# TC264Sheet.net
KiCad netlist of a schematic drawn in Altium Designer
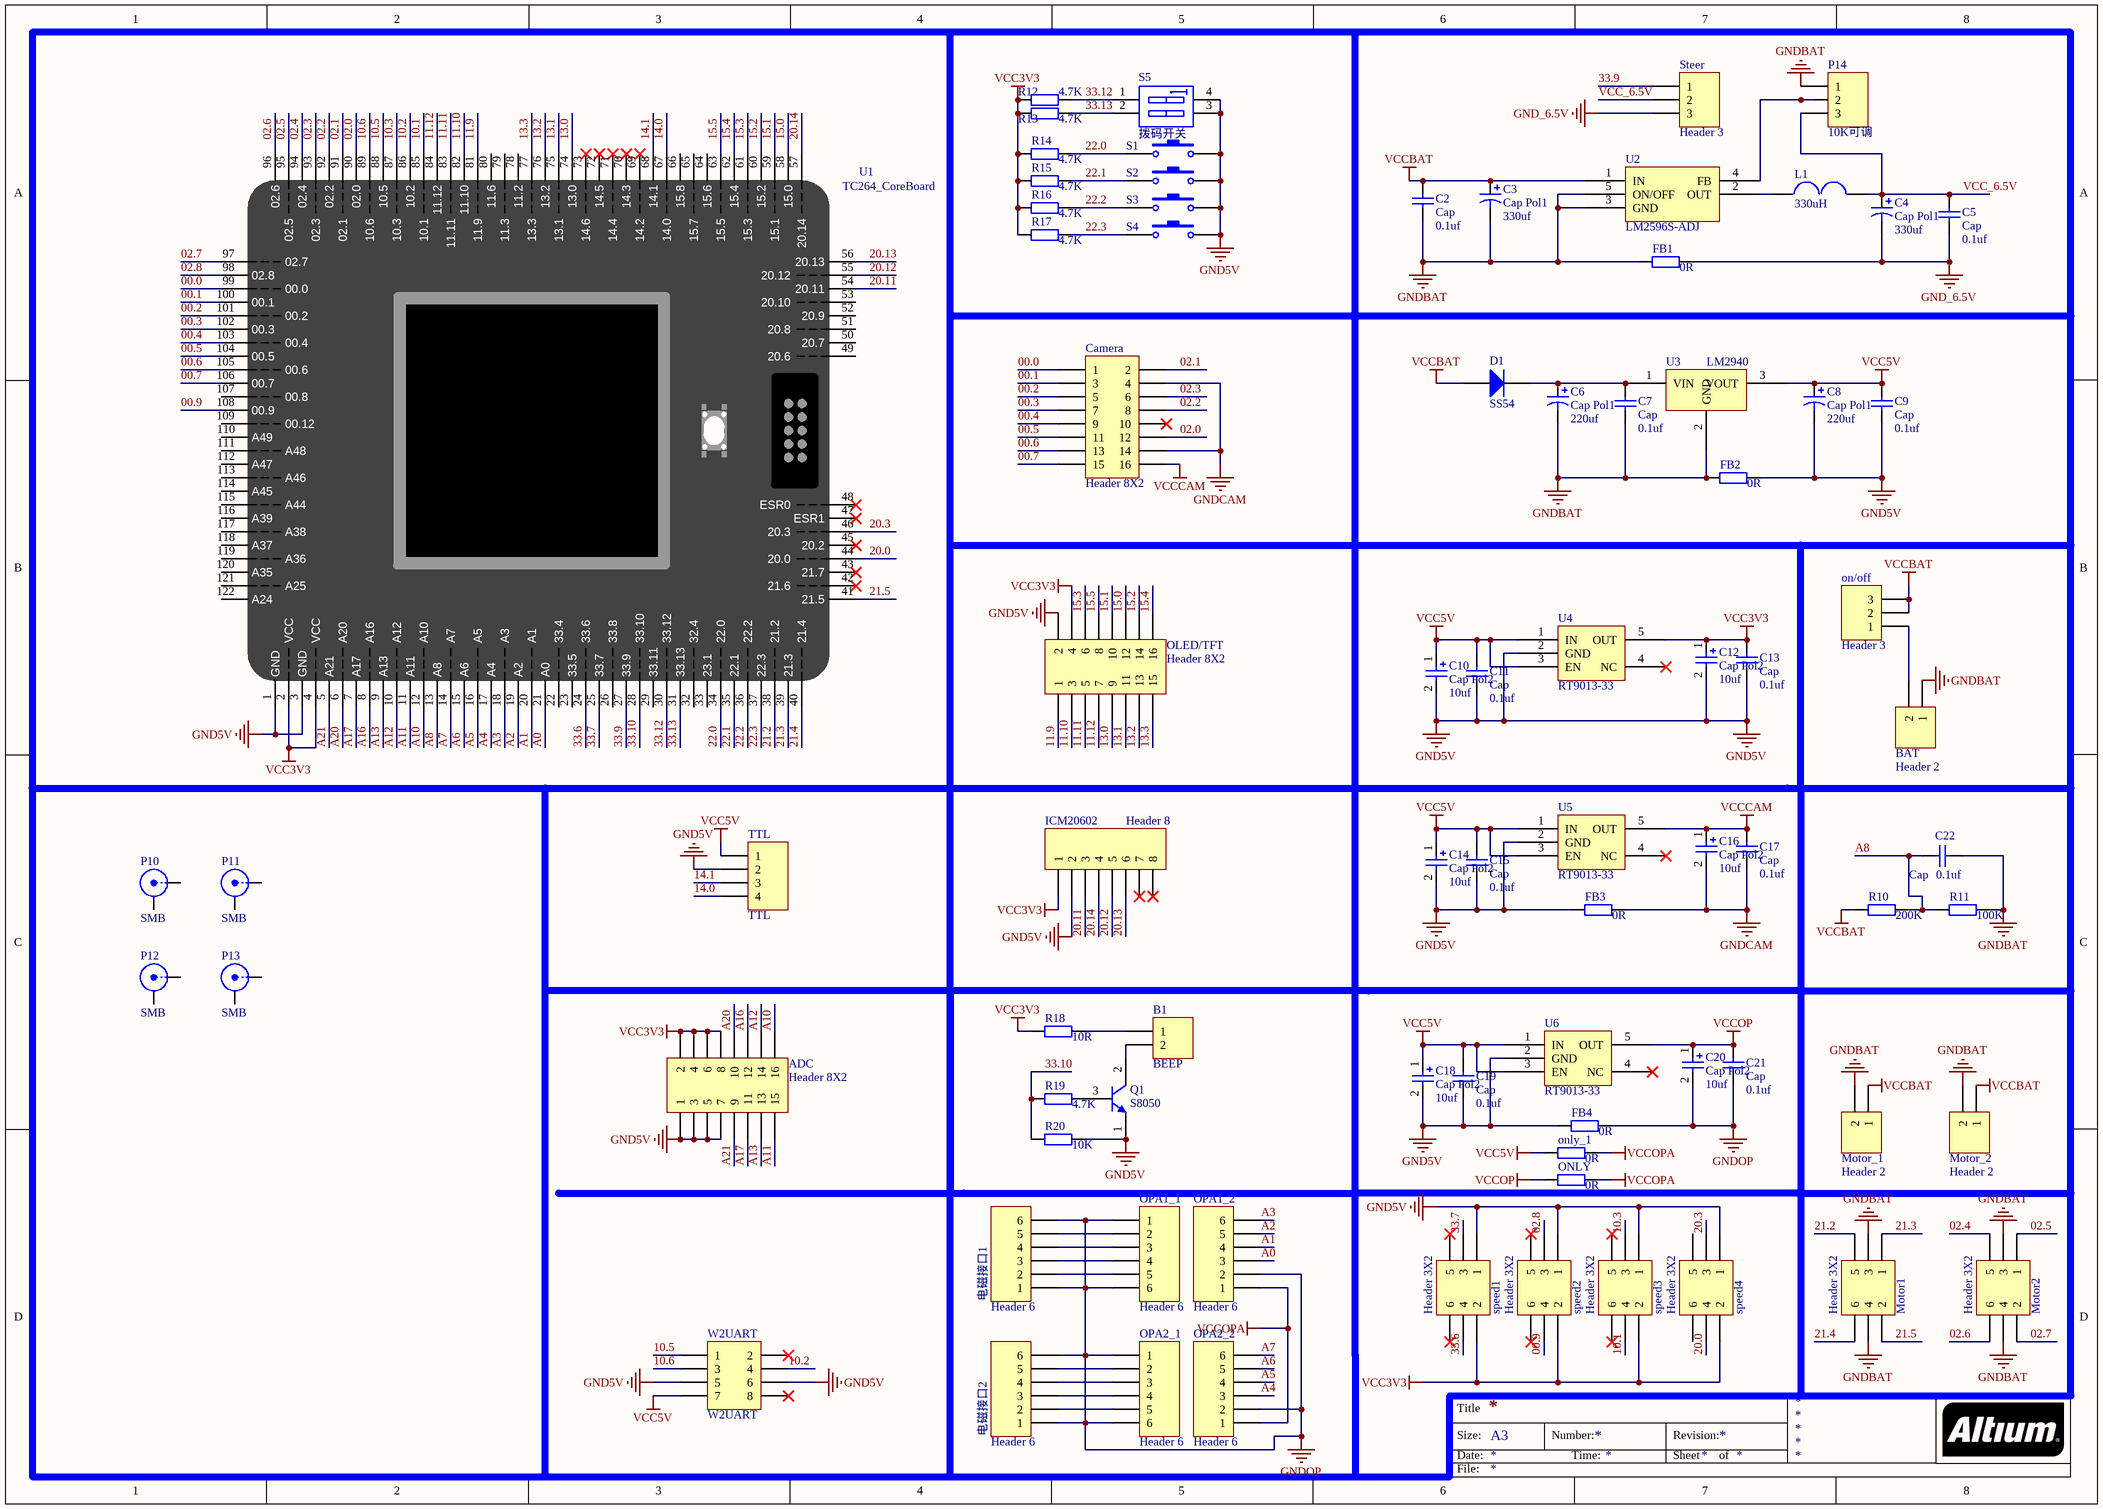
[diagram p0: TC264Sheet.SchDoc]

(export (version "E")
  (design (tool "Eeschema 10.0.6"))
  (components
    (comp (ref "ADC")
      (value "Header 8X2")
      (footprint "HDR2.54-M-LS-2x8P")
      (description "Header, 8-Pin, Dual row")
      (fields (field (name "PUBLISHER") "Altium Limited"))
      (libsource (lib "") (part "Header 8X2_1"))
    )
    (comp (ref "B1")
      (value "BEEP")
      (footprint "9*11mm有源蜂鸣器")
      (description "Header, 2-Pin")
      (fields (field (name "PUBLISHER") "Altium Limited"))
      (libsource (lib "") (part "Header 2_1"))
    )
    (comp (ref "BAT")
      (value "Header 2")
      (footprint "电源端口")
      (description "Header, 2-Pin")
      (fields (field (name "PUBLISHER") "Altium Limited"))
      (libsource (lib "Miscellaneous Connectors") (part "Header 2"))
    )
    (comp (ref "C2")
      (value "Cap")
      (footprint "0603电容_")
      (description "Capacitor")
      (fields (field (name "ALTIUM_VALUE") "0.1uf") (field (name "PUBLISHER") "Altium Limited"))
      (libsource (lib "Miscellaneous Devices") (part "Cap"))
    )
    (comp (ref "C3")
      (value "Cap Pol1")
      (footprint "470UF")
      (description "Polarized Capacitor (Radial)")
      (fields (field (name "ALTIUM_VALUE") "330uf") (field (name "PUBLISHER") "Altium Limited"))
      (libsource (lib "Miscellaneous Devices") (part "Cap Pol1"))
    )
    (comp (ref "C4")
      (value "Cap Pol1")
      (footprint "470UF")
      (description "Polarized Capacitor (Radial)")
      (fields (field (name "ALTIUM_VALUE") "330uf") (field (name "PUBLISHER") "Altium Limited"))
      (libsource (lib "Miscellaneous Devices") (part "Cap Pol1"))
    )
    (comp (ref "C5")
      (value "Cap")
      (footprint "0603电容_")
      (description "Capacitor")
      (fields (field (name "ALTIUM_VALUE") "0.1uf") (field (name "PUBLISHER") "Altium Limited"))
      (libsource (lib "Miscellaneous Devices") (part "Cap"))
    )
    (comp (ref "C6")
      (value "Cap Pol1")
      (footprint "470UF")
      (description "Polarized Capacitor (Radial)")
      (fields (field (name "ALTIUM_VALUE") "220uf") (field (name "PUBLISHER") "Altium Limited"))
      (libsource (lib "Miscellaneous Devices") (part "Cap Pol1"))
    )
    (comp (ref "C7")
      (value "Cap")
      (footprint "0603电容_")
      (description "Capacitor")
      (fields (field (name "ALTIUM_VALUE") "0.1uf") (field (name "PUBLISHER") "Altium Limited"))
      (libsource (lib "Miscellaneous Devices") (part "Cap"))
    )
    (comp (ref "C8")
      (value "Cap Pol1")
      (footprint "470UF")
      (description "Polarized Capacitor (Radial)")
      (fields (field (name "ALTIUM_VALUE") "220uf") (field (name "PUBLISHER") "Altium Limited"))
      (libsource (lib "Miscellaneous Devices") (part "Cap Pol1"))
    )
    (comp (ref "C9")
      (value "Cap")
      (footprint "0603电容_")
      (description "Capacitor")
      (fields (field (name "ALTIUM_VALUE") "0.1uf") (field (name "PUBLISHER") "Altium Limited"))
      (libsource (lib "Miscellaneous Devices") (part "Cap"))
    )
    (comp (ref "C10")
      (value "Cap Pol2")
      (footprint "10UF钽电容")
      (description "Polarized Capacitor (Axial)")
      (fields (field (name "ALTIUM_VALUE") "10uf") (field (name "PUBLISHER") "Altium Limited"))
      (libsource (lib "Miscellaneous Devices") (part "Cap Pol2"))
    )
    (comp (ref "C11")
      (value "Cap")
      (footprint "0603电容_")
      (description "Capacitor")
      (fields (field (name "ALTIUM_VALUE") "0.1uf") (field (name "PUBLISHER") "Altium Limited"))
      (libsource (lib "Miscellaneous Devices") (part "Cap"))
    )
    (comp (ref "C12")
      (value "Cap Pol2")
      (footprint "10UF钽电容")
      (description "Polarized Capacitor (Axial)")
      (fields (field (name "ALTIUM_VALUE") "10uf") (field (name "PUBLISHER") "Altium Limited"))
      (libsource (lib "Miscellaneous Devices") (part "Cap Pol2"))
    )
    (comp (ref "C13")
      (value "Cap")
      (footprint "0603电容_")
      (description "Capacitor")
      (fields (field (name "ALTIUM_VALUE") "0.1uf") (field (name "PUBLISHER") "Altium Limited"))
      (libsource (lib "Miscellaneous Devices") (part "Cap"))
    )
    (comp (ref "C14")
      (value "Cap Pol2")
      (footprint "10UF钽电容")
      (description "Polarized Capacitor (Axial)")
      (fields (field (name "ALTIUM_VALUE") "10uf") (field (name "PUBLISHER") "Altium Limited"))
      (libsource (lib "Miscellaneous Devices") (part "Cap Pol2"))
    )
    (comp (ref "C15")
      (value "Cap")
      (footprint "0603电容_")
      (description "Capacitor")
      (fields (field (name "ALTIUM_VALUE") "0.1uf") (field (name "PUBLISHER") "Altium Limited"))
      (libsource (lib "Miscellaneous Devices") (part "Cap"))
    )
    (comp (ref "C16")
      (value "Cap Pol2")
      (footprint "10UF钽电容")
      (description "Polarized Capacitor (Axial)")
      (fields (field (name "ALTIUM_VALUE") "10uf") (field (name "PUBLISHER") "Altium Limited"))
      (libsource (lib "Miscellaneous Devices") (part "Cap Pol2"))
    )
    (comp (ref "C17")
      (value "Cap")
      (footprint "0603电容_")
      (description "Capacitor")
      (fields (field (name "ALTIUM_VALUE") "0.1uf") (field (name "PUBLISHER") "Altium Limited"))
      (libsource (lib "Miscellaneous Devices") (part "Cap"))
    )
    (comp (ref "C18")
      (value "Cap Pol2")
      (footprint "10UF钽电容")
      (description "Polarized Capacitor (Axial)")
      (fields (field (name "ALTIUM_VALUE") "10uf") (field (name "PUBLISHER") "Altium Limited"))
      (libsource (lib "Miscellaneous Devices") (part "Cap Pol2"))
    )
    (comp (ref "C19")
      (value "Cap")
      (footprint "0603电容_")
      (description "Capacitor")
      (fields (field (name "ALTIUM_VALUE") "0.1uf") (field (name "PUBLISHER") "Altium Limited"))
      (libsource (lib "Miscellaneous Devices") (part "Cap"))
    )
    (comp (ref "C20")
      (value "Cap Pol2")
      (footprint "10UF钽电容")
      (description "Polarized Capacitor (Axial)")
      (fields (field (name "ALTIUM_VALUE") "10uf") (field (name "PUBLISHER") "Altium Limited"))
      (libsource (lib "Miscellaneous Devices") (part "Cap Pol2"))
    )
    (comp (ref "C21")
      (value "Cap")
      (footprint "0603电容_")
      (description "Capacitor")
      (fields (field (name "ALTIUM_VALUE") "0.1uf") (field (name "PUBLISHER") "Altium Limited"))
      (libsource (lib "Miscellaneous Devices") (part "Cap"))
    )
    (comp (ref "C22")
      (value "Cap")
      (footprint "0603电容_")
      (description "Capacitor")
      (fields (field (name "ALTIUM_VALUE") "0.1uf") (field (name "PUBLISHER") "Altium Limited"))
      (libsource (lib "Miscellaneous Devices") (part "Cap"))
    )
    (comp (ref "Camera")
      (value "Header 8X2")
      (footprint "HDR2.54-M-LS-2x8P")
      (description "Header, 8-Pin, Dual row")
      (fields (field (name "PUBLISHER") "Altium Limited"))
      (libsource (lib "Miscellaneous Connectors") (part "Header 8X2"))
    )
    (comp (ref "D1")
      (value "SS54")
      (footprint "in5819_SLFK")
      (description "3 Amp General Purpose Rectifier")
      (fields (field (name "PUBLISHER") "Altium Limited"))
      (libsource (lib "Miscellaneous Devices") (part "Diode 1N5404"))
    )
    (comp (ref "FB1")
      (value "0R")
      (footprint "0603电阻_")
      (description "Resistor")
      (fields (field (name "PUBLISHER") "Altium Limited"))
      (libsource (lib "Miscellaneous Devices") (part "Res2"))
    )
    (comp (ref "FB2")
      (value "0R")
      (footprint "0603电阻_")
      (description "Resistor")
      (fields (field (name "PUBLISHER") "Altium Limited"))
      (libsource (lib "Miscellaneous Devices") (part "Res2"))
    )
    (comp (ref "FB3")
      (value "0R")
      (footprint "0603电阻_")
      (description "Resistor")
      (fields (field (name "PUBLISHER") "Altium Limited"))
      (libsource (lib "Miscellaneous Devices") (part "Res2"))
    )
    (comp (ref "FB4")
      (value "0R")
      (footprint "0603电阻_")
      (description "Resistor")
      (fields (field (name "PUBLISHER") "Altium Limited"))
      (libsource (lib "Miscellaneous Devices") (part "Res2"))
    )
    (comp (ref "ICM20602")
      (value "Header 8")
      (footprint "HDR1X8")
      (description "Header, 8-Pin")
      (fields (field (name "PUBLISHER") "Altium Limited"))
      (libsource (lib "Miscellaneous Connectors") (part "Header 8"))
    )
    (comp (ref "L1") (value "330uH") (footprint "330uH") (libsource (lib "TC264Schlib") (part "330uH")))
    (comp (ref "Motor1")
      (value "Header 3X2")
      (footprint "HDR2.54-M-LS-2x3P")
      (description "Header, 3-Pin, Dual row")
      (fields (field (name "PUBLISHER") "Altium Limited"))
      (libsource (lib "Miscellaneous Connectors") (part "Header 3X2"))
    )
    (comp (ref "Motor2")
      (value "Header 3X2")
      (footprint "HDR2.54-M-LS-2x3P")
      (description "Header, 3-Pin, Dual row")
      (fields (field (name "PUBLISHER") "Altium Limited"))
      (libsource (lib "Miscellaneous Connectors") (part "Header 3X2"))
    )
    (comp (ref "Motor_1")
      (value "Header 2")
      (footprint "电源端口")
      (description "Header, 2-Pin")
      (fields (field (name "PUBLISHER") "Altium Limited"))
      (libsource (lib "Miscellaneous Connectors") (part "Header 2"))
    )
    (comp (ref "Motor_2")
      (value "Header 2")
      (footprint "电源端口")
      (description "Header, 2-Pin")
      (fields (field (name "PUBLISHER") "Altium Limited"))
      (libsource (lib "Miscellaneous Connectors") (part "Header 2"))
    )
    (comp (ref "OLED/TFT")
      (value "Header 8X2")
      (footprint "HDR2.54-M-LS-2x8P")
      (description "Header, 8-Pin, Dual row")
      (fields (field (name "PUBLISHER") "Altium Limited"))
      (libsource (lib "") (part "Header 8X2_1"))
    )
    (comp (ref "on/off")
      (value "Header 3")
      (footprint "小扭子开关")
      (description "Header, 3-Pin")
      (fields (field (name "PUBLISHER") "Altium Limited"))
      (libsource (lib "Miscellaneous Connectors") (part "Header 3"))
    )
    (comp (ref "ONLY")
      (value "0R")
      (footprint "0603电阻_")
      (description "Resistor")
      (fields (field (name "PUBLISHER") "Altium Limited"))
      (libsource (lib "Miscellaneous Devices") (part "Res2"))
    )
    (comp (ref "only_1")
      (value "0R")
      (footprint "0603电阻_")
      (description "Resistor")
      (fields (field (name "PUBLISHER") "Altium Limited"))
      (libsource (lib "Miscellaneous Devices") (part "Res2"))
    )
    (comp (ref "OPA1_1")
      (value "Header 6")
      (footprint "HDR1X6")
      (description "Header, 6-Pin")
      (fields (field (name "PUBLISHER") "Altium Limited"))
      (libsource (lib "") (part "Header 6_1"))
    )
    (comp (ref "OPA1_2")
      (value "Header 6")
      (footprint "HDR1X6")
      (description "Header, 6-Pin")
      (fields (field (name "PUBLISHER") "Altium Limited"))
      (libsource (lib "Miscellaneous Connectors") (part "Header 6"))
    )
    (comp (ref "OPA2_1")
      (value "Header 6")
      (footprint "HDR1X6")
      (description "Header, 6-Pin")
      (fields (field (name "PUBLISHER") "Altium Limited"))
      (libsource (lib "") (part "Header 6_1"))
    )
    (comp (ref "OPA2_2")
      (value "Header 6")
      (footprint "HDR1X6")
      (description "Header, 6-Pin")
      (fields (field (name "PUBLISHER") "Altium Limited"))
      (libsource (lib "Miscellaneous Connectors") (part "Header 6"))
    )
    (comp (ref "P10")
      (value "SMB")
      (footprint "螺丝孔")
      (description "SMB Straight Connector")
      (fields (field (name "PUBLISHER") "Altium Limited"))
      (libsource (lib "Miscellaneous Connectors") (part "SMB"))
    )
    (comp (ref "P11")
      (value "SMB")
      (footprint "螺丝孔")
      (description "SMB Straight Connector")
      (fields (field (name "PUBLISHER") "Altium Limited"))
      (libsource (lib "Miscellaneous Connectors") (part "SMB"))
    )
    (comp (ref "P12")
      (value "SMB")
      (footprint "螺丝孔")
      (description "SMB Straight Connector")
      (fields (field (name "PUBLISHER") "Altium Limited"))
      (libsource (lib "Miscellaneous Connectors") (part "SMB"))
    )
    (comp (ref "P13")
      (value "SMB")
      (footprint "螺丝孔")
      (description "SMB Straight Connector")
      (fields (field (name "PUBLISHER") "Altium Limited"))
      (libsource (lib "Miscellaneous Connectors") (part "SMB"))
    )
    (comp (ref "P14")
      (value "10K可调")
      (footprint "白兰可调电阻")
      (description "Header, 3-Pin")
      (fields (field (name "PUBLISHER") "Altium Limited"))
      (libsource (lib "") (part "Header 3_1"))
    )
    (comp (ref "Q1")
      (value "S8050")
      (footprint "SI2302")
      (description "NPN General Purpose Amplifier")
      (fields (field (name "PUBLISHER") "Altium Limited"))
      (libsource (lib "Miscellaneous Devices") (part "2N3904"))
    )
    (comp (ref "R10")
      (value "200K")
      (footprint "0603电阻_")
      (description "Resistor")
      (fields (field (name "PUBLISHER") "Altium Limited"))
      (libsource (lib "Miscellaneous Devices") (part "Res2"))
    )
    (comp (ref "R11")
      (value "100K")
      (footprint "0603电阻_")
      (description "Resistor")
      (fields (field (name "PUBLISHER") "Altium Limited"))
      (libsource (lib "Miscellaneous Devices") (part "Res2"))
    )
    (comp (ref "R12")
      (value "4.7K")
      (footprint "0603电阻_")
      (description "Resistor")
      (fields (field (name "PUBLISHER") "Altium Limited"))
      (libsource (lib "Miscellaneous Devices") (part "Res2"))
    )
    (comp (ref "R13")
      (value "4.7K")
      (footprint "0603电阻_")
      (description "Resistor")
      (fields (field (name "PUBLISHER") "Altium Limited"))
      (libsource (lib "Miscellaneous Devices") (part "Res2"))
    )
    (comp (ref "R14")
      (value "4.7K")
      (footprint "0603电阻_")
      (description "Resistor")
      (fields (field (name "PUBLISHER") "Altium Limited"))
      (libsource (lib "Miscellaneous Devices") (part "Res2"))
    )
    (comp (ref "R15")
      (value "4.7K")
      (footprint "0603电阻_")
      (description "Resistor")
      (fields (field (name "PUBLISHER") "Altium Limited"))
      (libsource (lib "Miscellaneous Devices") (part "Res2"))
    )
    (comp (ref "R16")
      (value "4.7K")
      (footprint "0603电阻_")
      (description "Resistor")
      (fields (field (name "PUBLISHER") "Altium Limited"))
      (libsource (lib "Miscellaneous Devices") (part "Res2"))
    )
    (comp (ref "R17")
      (value "4.7K")
      (footprint "0603电阻_")
      (description "Resistor")
      (fields (field (name "PUBLISHER") "Altium Limited"))
      (libsource (lib "Miscellaneous Devices") (part "Res2"))
    )
    (comp (ref "R18")
      (value "10R")
      (footprint "0603电阻_")
      (description "Resistor")
      (fields (field (name "PUBLISHER") "Altium Limited"))
      (libsource (lib "Miscellaneous Devices") (part "Res2"))
    )
    (comp (ref "R19")
      (value "4.7K")
      (footprint "0603电阻_")
      (description "Resistor")
      (fields (field (name "PUBLISHER") "Altium Limited"))
      (libsource (lib "Miscellaneous Devices") (part "Res2"))
    )
    (comp (ref "R20")
      (value "10K")
      (footprint "0603电阻_")
      (description "Resistor")
      (fields (field (name "PUBLISHER") "Altium Limited"))
      (libsource (lib "Miscellaneous Devices") (part "Res2"))
    )
    (comp (ref "S1")
      (value "~")
      (footprint "3*4*2贴片轻触按键")
      (description "Switch")
      (fields (field (name "PUBLISHER") "Altium Limited"))
      (libsource (lib "Miscellaneous Devices") (part "SW-PB"))
    )
    (comp (ref "S2")
      (value "~")
      (footprint "3*4*2贴片轻触按键")
      (description "Switch")
      (fields (field (name "PUBLISHER") "Altium Limited"))
      (libsource (lib "Miscellaneous Devices") (part "SW-PB"))
    )
    (comp (ref "S3")
      (value "~")
      (footprint "3*4*2贴片轻触按键")
      (description "Switch")
      (fields (field (name "PUBLISHER") "Altium Limited"))
      (libsource (lib "Miscellaneous Devices") (part "SW-PB"))
    )
    (comp (ref "S4")
      (value "~")
      (footprint "3*4*2贴片轻触按键")
      (description "Switch")
      (fields (field (name "PUBLISHER") "Altium Limited"))
      (libsource (lib "Miscellaneous Devices") (part "SW-PB"))
    )
    (comp (ref "S5")
      (value "拨码开关")
      (footprint "2pin拨码开关2.54_SMT")
      (description "DIP Switch, 2 Position, SPST")
      (fields (field (name "PUBLISHER") "Altium Limited"))
      (libsource (lib "Miscellaneous Devices") (part "SW DIP-2"))
    )
    (comp (ref "speed1")
      (value "Header 3X2")
      (footprint "HDR2.54-M-LS-2x3P")
      (description "Header, 3-Pin, Dual row")
      (fields (field (name "PUBLISHER") "Altium Limited"))
      (libsource (lib "Miscellaneous Connectors") (part "Header 3X2"))
    )
    (comp (ref "speed2")
      (value "Header 3X2")
      (footprint "HDR2.54-M-LS-2x3P")
      (description "Header, 3-Pin, Dual row")
      (fields (field (name "PUBLISHER") "Altium Limited"))
      (libsource (lib "Miscellaneous Connectors") (part "Header 3X2"))
    )
    (comp (ref "speed3")
      (value "Header 3X2")
      (footprint "HDR2.54-M-LS-2x3P")
      (description "Header, 3-Pin, Dual row")
      (fields (field (name "PUBLISHER") "Altium Limited"))
      (libsource (lib "Miscellaneous Connectors") (part "Header 3X2"))
    )
    (comp (ref "speed4")
      (value "Header 3X2")
      (footprint "HDR2.54-M-LS-2x3P")
      (description "Header, 3-Pin, Dual row")
      (fields (field (name "PUBLISHER") "Altium Limited"))
      (libsource (lib "Miscellaneous Connectors") (part "Header 3X2"))
    )
    (comp (ref "Steer")
      (value "Header 3")
      (footprint "HDR1X3")
      (description "Header, 3-Pin")
      (fields (field (name "PUBLISHER") "Altium Limited"))
      (libsource (lib "") (part "Header 3_1"))
    )
    (comp (ref "TTL")
      (value "TTL")
      (footprint "HDR1X4")
      (description "Header, 4-Pin")
      (fields (field (name "PUBLISHER") "Altium Limited"))
      (libsource (lib "Miscellaneous Connectors") (part "Header 4"))
    )
    (comp (ref "U1")
      (value "TC264_CoreBoard")
      (footprint "TC264_CoreBoard")
      (description "逐飞科技TC264核心板")
      (libsource (lib "TC264_CoreBoard") (part "TC264_CoreBoard"))
    )
    (comp (ref "U2")
      (value "LM2596S-ADJ")
      (footprint "TO263-5")
      (libsource (lib "TC264Schlib") (part "LM2596S"))
    )
    (comp (ref "U3")
      (value "LM2940")
      (footprint "LM2940-5.0")
      (libsource (lib "TC264Schlib") (part "LM2940"))
    )
    (comp (ref "U4")
      (value "RT9013-33")
      (footprint "SOT-23-5")
      (libsource (lib "TC264Schlib") (part "RT9013-33"))
    )
    (comp (ref "U5")
      (value "RT9013-33")
      (footprint "SOT-23-5")
      (libsource (lib "TC264Schlib") (part "RT9013-33"))
    )
    (comp (ref "U6")
      (value "RT9013-33")
      (footprint "SOT-23-5")
      (libsource (lib "TC264Schlib") (part "RT9013-33"))
    )
    (comp (ref "W2UART")
      (value "W2UART")
      (footprint "HDR2.54-M-LS-2x4P")
      (description "Header, 4-Pin, Dual row")
      (fields (field (name "PUBLISHER") "Altium Limited"))
      (libsource (lib "Miscellaneous Connectors") (part "Header 4X2"))
    )
    (comp (ref "电磁接口1")
      (value "Header 6")
      (footprint "HDR1X6")
      (description "Header, 6-Pin")
      (fields (field (name "PUBLISHER") "Altium Limited"))
      (libsource (lib "Miscellaneous Connectors") (part "Header 6"))
    )
    (comp (ref "电磁接口2")
      (value "Header 6")
      (footprint "HDR1X6")
      (description "Header, 6-Pin")
      (fields (field (name "PUBLISHER") "Altium Limited"))
      (libsource (lib "Miscellaneous Connectors") (part "Header 6"))
    )
  )
  (nets
    (net (code "1") (name "/00.0") (class "Default")
      (node (ref "Camera") (pin "1") (pinfunction "1_1") (pintype "passive"))
      (node (ref "U1") (pin "99") (pinfunction "00.0_99") (pintype "passive"))
    )
    (net (code "2") (name "/00.1") (class "Default")
      (node (ref "Camera") (pin "3") (pinfunction "3_3") (pintype "passive"))
      (node (ref "U1") (pin "100") (pinfunction "00.1_100") (pintype "passive"))
    )
    (net (code "3") (name "/00.2") (class "Default")
      (node (ref "Camera") (pin "5") (pinfunction "5_5") (pintype "passive"))
      (node (ref "U1") (pin "101") (pinfunction "00.2_101") (pintype "passive"))
    )
    (net (code "4") (name "/00.3") (class "Default")
      (node (ref "Camera") (pin "7") (pinfunction "7_7") (pintype "passive"))
      (node (ref "U1") (pin "102") (pinfunction "00.3_102") (pintype "passive"))
    )
    (net (code "5") (name "/00.4") (class "Default")
      (node (ref "Camera") (pin "9") (pinfunction "9_9") (pintype "passive"))
      (node (ref "U1") (pin "103") (pinfunction "00.4_103") (pintype "passive"))
    )
    (net (code "6") (name "/00.5") (class "Default")
      (node (ref "Camera") (pin "11") (pinfunction "11_11") (pintype "passive"))
      (node (ref "U1") (pin "104") (pinfunction "00.5_104") (pintype "passive"))
    )
    (net (code "7") (name "/00.6") (class "Default")
      (node (ref "Camera") (pin "13") (pinfunction "13_13") (pintype "passive"))
      (node (ref "U1") (pin "105") (pinfunction "00.6_105") (pintype "passive"))
    )
    (net (code "8") (name "/00.7") (class "Default")
      (node (ref "Camera") (pin "15") (pinfunction "15_15") (pintype "passive"))
      (node (ref "U1") (pin "106") (pinfunction "00.7_106") (pintype "passive"))
    )
    (net (code "9") (name "/00.9") (class "Default")
      (node (ref "U1") (pin "108") (pinfunction "00.9_108") (pintype "passive"))
      (node (ref "speed2") (pin "4") (pinfunction "4_4") (pintype "passive"))
    )
    (net (code "10") (name "/02.0") (class "Default")
      (node (ref "Camera") (pin "12") (pinfunction "12_12") (pintype "passive"))
      (node (ref "U1") (pin "90") (pinfunction "02.0_90") (pintype "passive"))
    )
    (net (code "11") (name "/02.1") (class "Default")
      (node (ref "Camera") (pin "2") (pinfunction "2_2") (pintype "passive"))
      (node (ref "U1") (pin "91") (pinfunction "02.1_91") (pintype "passive"))
    )
    (net (code "12") (name "/02.2") (class "Default")
      (node (ref "Camera") (pin "8") (pinfunction "8_8") (pintype "passive"))
      (node (ref "U1") (pin "92") (pinfunction "02.2_92") (pintype "passive"))
    )
    (net (code "13") (name "/02.3") (class "Default")
      (node (ref "Camera") (pin "6") (pinfunction "6_6") (pintype "passive"))
      (node (ref "U1") (pin "93") (pinfunction "02.3_93") (pintype "passive"))
    )
    (net (code "14") (name "/02.4") (class "Default")
      (node (ref "Motor2") (pin "5") (pinfunction "5_5") (pintype "passive"))
      (node (ref "U1") (pin "94") (pinfunction "02.4_94") (pintype "passive"))
    )
    (net (code "15") (name "/02.5") (class "Default")
      (node (ref "Motor2") (pin "1") (pinfunction "1_1") (pintype "passive"))
      (node (ref "U1") (pin "95") (pinfunction "02.5_95") (pintype "passive"))
    )
    (net (code "16") (name "/02.6") (class "Default")
      (node (ref "Motor2") (pin "6") (pinfunction "6_6") (pintype "passive"))
      (node (ref "U1") (pin "96") (pinfunction "02.6_96") (pintype "passive"))
    )
    (net (code "17") (name "/02.7") (class "Default")
      (node (ref "Motor2") (pin "2") (pinfunction "2_2") (pintype "passive"))
      (node (ref "U1") (pin "97") (pinfunction "02.7_97") (pintype "passive"))
    )
    (net (code "18") (name "/02.8") (class "Default")
      (node (ref "U1") (pin "98") (pinfunction "02.8_98") (pintype "passive"))
      (node (ref "speed2") (pin "3") (pinfunction "3_3") (pintype "passive"))
    )
    (net (code "19") (name "/10.1") (class "Default")
      (node (ref "U1") (pin "85") (pinfunction "10.1_85") (pintype "passive"))
      (node (ref "speed3") (pin "4") (pinfunction "4_4") (pintype "passive"))
    )
    (net (code "20") (name "/10.2") (class "Default")
      (node (ref "U1") (pin "86") (pinfunction "10.2_86") (pintype "passive"))
      (node (ref "W2UART") (pin "4") (pinfunction "4_4") (pintype "passive"))
    )
    (net (code "21") (name "/10.3") (class "Default")
      (node (ref "U1") (pin "87") (pinfunction "10.3_87") (pintype "passive"))
      (node (ref "speed3") (pin "3") (pinfunction "3_3") (pintype "passive"))
    )
    (net (code "22") (name "/10.5") (class "Default")
      (node (ref "U1") (pin "88") (pinfunction "10.5_88") (pintype "passive"))
      (node (ref "W2UART") (pin "1") (pinfunction "1_1") (pintype "passive"))
    )
    (net (code "23") (name "/10.6") (class "Default")
      (node (ref "U1") (pin "89") (pinfunction "10.6_89") (pintype "passive"))
      (node (ref "W2UART") (pin "3") (pinfunction "3_3") (pintype "passive"))
    )
    (net (code "24") (name "/11.9") (class "Default")
      (node (ref "OLED/TFT") (pin "1") (pinfunction "1_1") (pintype "passive"))
      (node (ref "U1") (pin "81") (pinfunction "11.9_81") (pintype "passive"))
    )
    (net (code "25") (name "/11.10") (class "Default")
      (node (ref "OLED/TFT") (pin "3") (pinfunction "3_3") (pintype "passive"))
      (node (ref "U1") (pin "82") (pinfunction "11.10_82") (pintype "passive"))
    )
    (net (code "26") (name "/11.11") (class "Default")
      (node (ref "OLED/TFT") (pin "5") (pinfunction "5_5") (pintype "passive"))
      (node (ref "U1") (pin "83") (pinfunction "11.11_83") (pintype "passive"))
    )
    (net (code "27") (name "/11.12") (class "Default")
      (node (ref "OLED/TFT") (pin "7") (pinfunction "7_7") (pintype "passive"))
      (node (ref "U1") (pin "84") (pinfunction "11.12_84") (pintype "passive"))
    )
    (net (code "28") (name "/13.0") (class "Default")
      (node (ref "OLED/TFT") (pin "9") (pinfunction "9_9") (pintype "passive"))
      (node (ref "U1") (pin "74") (pinfunction "13.0_74") (pintype "passive"))
    )
    (net (code "29") (name "/13.1") (class "Default")
      (node (ref "OLED/TFT") (pin "11") (pinfunction "11_11") (pintype "passive"))
      (node (ref "U1") (pin "75") (pinfunction "13.1_75") (pintype "passive"))
    )
    (net (code "30") (name "/13.2") (class "Default")
      (node (ref "OLED/TFT") (pin "13") (pinfunction "13_13") (pintype "passive"))
      (node (ref "U1") (pin "76") (pinfunction "13.2_76") (pintype "passive"))
    )
    (net (code "31") (name "/13.3") (class "Default")
      (node (ref "OLED/TFT") (pin "15") (pinfunction "15_15") (pintype "passive"))
      (node (ref "U1") (pin "77") (pinfunction "13.3_77") (pintype "passive"))
    )
    (net (code "32") (name "/14.0") (class "Default")
      (node (ref "TTL") (pin "4") (pinfunction "4_4") (pintype "passive"))
      (node (ref "U1") (pin "67") (pinfunction "14.0_67") (pintype "passive"))
    )
    (net (code "33") (name "/14.1") (class "Default")
      (node (ref "TTL") (pin "3") (pinfunction "3_3") (pintype "passive"))
      (node (ref "U1") (pin "68") (pinfunction "14.1_68") (pintype "passive"))
    )
    (net (code "34") (name "/15.0") (class "Default")
      (node (ref "OLED/TFT") (pin "12") (pinfunction "12_12") (pintype "passive"))
      (node (ref "U1") (pin "58") (pinfunction "15.0_58") (pintype "passive"))
    )
    (net (code "35") (name "/15.1") (class "Default")
      (node (ref "OLED/TFT") (pin "10") (pinfunction "10_10") (pintype "passive"))
      (node (ref "U1") (pin "59") (pinfunction "15.1_59") (pintype "passive"))
    )
    (net (code "36") (name "/15.2") (class "Default")
      (node (ref "OLED/TFT") (pin "14") (pinfunction "14_14") (pintype "passive"))
      (node (ref "U1") (pin "60") (pinfunction "15.2_60") (pintype "passive"))
    )
    (net (code "37") (name "/15.3") (class "Default")
      (node (ref "OLED/TFT") (pin "6") (pinfunction "6_6") (pintype "passive"))
      (node (ref "U1") (pin "61") (pinfunction "15.3_61") (pintype "passive"))
    )
    (net (code "38") (name "/15.4") (class "Default")
      (node (ref "OLED/TFT") (pin "16") (pinfunction "16_16") (pintype "passive"))
      (node (ref "U1") (pin "62") (pinfunction "15.4_62") (pintype "passive"))
    )
    (net (code "39") (name "/15.5") (class "Default")
      (node (ref "OLED/TFT") (pin "8") (pinfunction "8_8") (pintype "passive"))
      (node (ref "U1") (pin "63") (pinfunction "15.5_63") (pintype "passive"))
    )
    (net (code "40") (name "/20.0") (class "Default")
      (node (ref "U1") (pin "44") (pinfunction "20.0_44") (pintype "passive"))
      (node (ref "speed4") (pin "4") (pinfunction "4_4") (pintype "passive"))
    )
    (net (code "41") (name "/20.3") (class "Default")
      (node (ref "U1") (pin "46") (pinfunction "20.3_46") (pintype "passive"))
      (node (ref "speed4") (pin "3") (pinfunction "3_3") (pintype "passive"))
    )
    (net (code "42") (name "/20.11") (class "Default")
      (node (ref "ICM20602") (pin "3") (pinfunction "3_3") (pintype "passive"))
      (node (ref "U1") (pin "54") (pinfunction "20.11_54") (pintype "passive"))
    )
    (net (code "43") (name "/20.12") (class "Default")
      (node (ref "ICM20602") (pin "5") (pinfunction "5_5") (pintype "passive"))
      (node (ref "U1") (pin "55") (pinfunction "20.12_55") (pintype "passive"))
    )
    (net (code "44") (name "/20.13") (class "Default")
      (node (ref "ICM20602") (pin "6") (pinfunction "6_6") (pintype "passive"))
      (node (ref "U1") (pin "56") (pinfunction "20.13_56") (pintype "passive"))
    )
    (net (code "45") (name "/20.14") (class "Default")
      (node (ref "ICM20602") (pin "4") (pinfunction "4_4") (pintype "passive"))
      (node (ref "U1") (pin "57") (pinfunction "20.14_57") (pintype "passive"))
    )
    (net (code "46") (name "/21.2") (class "Default")
      (node (ref "Motor1") (pin "5") (pinfunction "5_5") (pintype "passive"))
      (node (ref "U1") (pin "38") (pinfunction "21.2_38") (pintype "passive"))
    )
    (net (code "47") (name "/21.3") (class "Default")
      (node (ref "Motor1") (pin "1") (pinfunction "1_1") (pintype "passive"))
      (node (ref "U1") (pin "39") (pinfunction "21.3_39") (pintype "passive"))
    )
    (net (code "48") (name "/21.4") (class "Default")
      (node (ref "Motor1") (pin "6") (pinfunction "6_6") (pintype "passive"))
      (node (ref "U1") (pin "40") (pinfunction "21.4_40") (pintype "passive"))
    )
    (net (code "49") (name "/21.5") (class "Default")
      (node (ref "Motor1") (pin "2") (pinfunction "2_2") (pintype "passive"))
      (node (ref "U1") (pin "41") (pinfunction "21.5_41") (pintype "passive"))
    )
    (net (code "50") (name "/22.0") (class "Default")
      (node (ref "R14") (pin "2") (pinfunction "2_2") (pintype "passive"))
      (node (ref "S1") (pin "1") (pinfunction "1_1") (pintype "passive"))
      (node (ref "U1") (pin "34") (pinfunction "22.0_34") (pintype "passive"))
    )
    (net (code "51") (name "/22.1") (class "Default")
      (node (ref "R15") (pin "2") (pinfunction "2_2") (pintype "passive"))
      (node (ref "S2") (pin "1") (pinfunction "1_1") (pintype "passive"))
      (node (ref "U1") (pin "35") (pinfunction "22.1_35") (pintype "passive"))
    )
    (net (code "52") (name "/22.2") (class "Default")
      (node (ref "R16") (pin "2") (pinfunction "2_2") (pintype "passive"))
      (node (ref "S3") (pin "1") (pinfunction "1_1") (pintype "passive"))
      (node (ref "U1") (pin "36") (pinfunction "22.2_36") (pintype "passive"))
    )
    (net (code "53") (name "/22.3") (class "Default")
      (node (ref "R17") (pin "2") (pinfunction "2_2") (pintype "passive"))
      (node (ref "S4") (pin "1") (pinfunction "1_1") (pintype "passive"))
      (node (ref "U1") (pin "37") (pinfunction "22.3_37") (pintype "passive"))
    )
    (net (code "54") (name "/33.6") (class "Default")
      (node (ref "U1") (pin "24") (pinfunction "33.6_24") (pintype "passive"))
      (node (ref "speed1") (pin "4") (pinfunction "4_4") (pintype "passive"))
    )
    (net (code "55") (name "/33.7") (class "Default")
      (node (ref "U1") (pin "25") (pinfunction "33.7_25") (pintype "passive"))
      (node (ref "speed1") (pin "3") (pinfunction "3_3") (pintype "passive"))
    )
    (net (code "56") (name "/33.9") (class "Default")
      (node (ref "Steer") (pin "1") (pinfunction "1_1") (pintype "passive"))
      (node (ref "U1") (pin "27") (pinfunction "33.9_27") (pintype "passive"))
    )
    (net (code "57") (name "/33.10") (class "Default")
      (node (ref "R19") (pin "1") (pinfunction "1_1") (pintype "passive"))
      (node (ref "R20") (pin "1") (pinfunction "1_1") (pintype "passive"))
      (node (ref "U1") (pin "28") (pinfunction "33.10_28") (pintype "passive"))
    )
    (net (code "58") (name "/33.12") (class "Default")
      (node (ref "R12") (pin "2") (pinfunction "2_2") (pintype "passive"))
      (node (ref "S5") (pin "1") (pinfunction "A1_1") (pintype "passive"))
      (node (ref "U1") (pin "30") (pinfunction "33.12_30") (pintype "passive"))
    )
    (net (code "59") (name "/33.13") (class "Default")
      (node (ref "R13") (pin "2") (pinfunction "2_2") (pintype "passive"))
      (node (ref "S5") (pin "2") (pinfunction "A2_2") (pintype "passive"))
      (node (ref "U1") (pin "31") (pinfunction "33.13_31") (pintype "passive"))
    )
    (net (code "60") (name "/A0") (class "Default")
      (node (ref "OPA1_2") (pin "3") (pinfunction "3_3") (pintype "passive"))
      (node (ref "U1") (pin "21") (pinfunction "A0_21") (pintype "passive"))
    )
    (net (code "61") (name "/A1") (class "Default")
      (node (ref "OPA1_2") (pin "4") (pinfunction "4_4") (pintype "passive"))
      (node (ref "U1") (pin "20") (pinfunction "A1_20") (pintype "passive"))
    )
    (net (code "62") (name "/A2") (class "Default")
      (node (ref "OPA1_2") (pin "5") (pinfunction "5_5") (pintype "passive"))
      (node (ref "U1") (pin "19") (pinfunction "A2_19") (pintype "passive"))
    )
    (net (code "63") (name "/A3") (class "Default")
      (node (ref "OPA1_2") (pin "6") (pinfunction "6_6") (pintype "passive"))
      (node (ref "U1") (pin "18") (pinfunction "A3_18") (pintype "passive"))
    )
    (net (code "64") (name "/A4") (class "Default")
      (node (ref "OPA2_2") (pin "3") (pinfunction "3_3") (pintype "passive"))
      (node (ref "U1") (pin "17") (pinfunction "A4_17") (pintype "passive"))
    )
    (net (code "65") (name "/A5") (class "Default")
      (node (ref "OPA2_2") (pin "4") (pinfunction "4_4") (pintype "passive"))
      (node (ref "U1") (pin "16") (pinfunction "A5_16") (pintype "passive"))
    )
    (net (code "66") (name "/A6") (class "Default")
      (node (ref "OPA2_2") (pin "5") (pinfunction "5_5") (pintype "passive"))
      (node (ref "U1") (pin "15") (pinfunction "A6_15") (pintype "passive"))
    )
    (net (code "67") (name "/A7") (class "Default")
      (node (ref "OPA2_2") (pin "6") (pinfunction "6_6") (pintype "passive"))
      (node (ref "U1") (pin "14") (pinfunction "A7_14") (pintype "passive"))
    )
    (net (code "68") (name "/A8") (class "Default")
      (node (ref "C22") (pin "2") (pinfunction "2_2") (pintype "passive"))
      (node (ref "R10") (pin "2") (pinfunction "2_2") (pintype "passive"))
      (node (ref "R11") (pin "1") (pinfunction "1_1") (pintype "passive"))
      (node (ref "U1") (pin "13") (pinfunction "A8_13") (pintype "passive"))
    )
    (net (code "69") (name "/A10") (class "Default")
      (node (ref "ADC") (pin "16") (pinfunction "16_16") (pintype "passive"))
      (node (ref "U1") (pin "12") (pinfunction "A10_12") (pintype "passive"))
    )
    (net (code "70") (name "/A11") (class "Default")
      (node (ref "ADC") (pin "15") (pinfunction "15_15") (pintype "passive"))
      (node (ref "U1") (pin "11") (pinfunction "A11_11") (pintype "passive"))
    )
    (net (code "71") (name "/A12") (class "Default")
      (node (ref "ADC") (pin "14") (pinfunction "14_14") (pintype "passive"))
      (node (ref "U1") (pin "10") (pinfunction "A12_10") (pintype "passive"))
    )
    (net (code "72") (name "/A13") (class "Default")
      (node (ref "ADC") (pin "13") (pinfunction "13_13") (pintype "passive"))
      (node (ref "U1") (pin "9") (pinfunction "A13_9") (pintype "passive"))
    )
    (net (code "73") (name "/A16") (class "Default")
      (node (ref "ADC") (pin "12") (pinfunction "12_12") (pintype "passive"))
      (node (ref "U1") (pin "8") (pinfunction "A16_8") (pintype "passive"))
    )
    (net (code "74") (name "/A17") (class "Default")
      (node (ref "ADC") (pin "11") (pinfunction "11_11") (pintype "passive"))
      (node (ref "U1") (pin "7") (pinfunction "A17_7") (pintype "passive"))
    )
    (net (code "75") (name "/A20") (class "Default")
      (node (ref "ADC") (pin "10") (pinfunction "10_10") (pintype "passive"))
      (node (ref "U1") (pin "6") (pinfunction "A20_6") (pintype "passive"))
    )
    (net (code "76") (name "/A21") (class "Default")
      (node (ref "ADC") (pin "9") (pinfunction "9_9") (pintype "passive"))
      (node (ref "U1") (pin "5") (pinfunction "A21_5") (pintype "passive"))
    )
    (net (code "77") (name "/VCC_6.5V") (class "Default")
      (node (ref "C4") (pin "1") (pinfunction "1_1") (pintype "passive"))
      (node (ref "C5") (pin "2") (pinfunction "2_2") (pintype "passive"))
      (node (ref "L1") (pin "2") (pintype "open_collector"))
      (node (ref "P14") (pin "3") (pinfunction "3_3") (pintype "passive"))
      (node (ref "Steer") (pin "2") (pinfunction "2_2") (pintype "passive"))
    )
    (net (code "78") (name "GND5V") (class "Default")
      (node (ref "ADC") (pin "1") (pinfunction "1_1") (pintype "passive"))
      (node (ref "ADC") (pin "3") (pinfunction "3_3") (pintype "passive"))
      (node (ref "ADC") (pin "5") (pinfunction "5_5") (pintype "passive"))
      (node (ref "ADC") (pin "7") (pinfunction "7_7") (pintype "passive"))
      (node (ref "C10") (pin "2") (pinfunction "2_2") (pintype "passive"))
      (node (ref "C11") (pin "1") (pinfunction "1_1") (pintype "passive"))
      (node (ref "C12") (pin "2") (pinfunction "2_2") (pintype "passive"))
      (node (ref "C13") (pin "1") (pinfunction "1_1") (pintype "passive"))
      (node (ref "C14") (pin "2") (pinfunction "2_2") (pintype "passive"))
      (node (ref "C15") (pin "1") (pinfunction "1_1") (pintype "passive"))
      (node (ref "C18") (pin "2") (pinfunction "2_2") (pintype "passive"))
      (node (ref "C19") (pin "1") (pinfunction "1_1") (pintype "passive"))
      (node (ref "C8") (pin "2") (pinfunction "2_2") (pintype "passive"))
      (node (ref "C9") (pin "1") (pinfunction "1_1") (pintype "passive"))
      (node (ref "FB2") (pin "2") (pinfunction "2_2") (pintype "passive"))
      (node (ref "FB3") (pin "1") (pinfunction "1_1") (pintype "passive"))
      (node (ref "FB4") (pin "1") (pinfunction "1_1") (pintype "passive"))
      (node (ref "ICM20602") (pin "2") (pinfunction "2_2") (pintype "passive"))
      (node (ref "OLED/TFT") (pin "2") (pinfunction "2_2") (pintype "passive"))
      (node (ref "Q1") (pin "1") (pinfunction "E_1") (pintype "passive"))
      (node (ref "R20") (pin "2") (pinfunction "2_2") (pintype "passive"))
      (node (ref "S1") (pin "2") (pinfunction "2_2") (pintype "passive"))
      (node (ref "S2") (pin "2") (pinfunction "2_2") (pintype "passive"))
      (node (ref "S3") (pin "2") (pinfunction "2_2") (pintype "passive"))
      (node (ref "S4") (pin "2") (pinfunction "2_2") (pintype "passive"))
      (node (ref "S5") (pin "3") (pinfunction "B2_3") (pintype "passive"))
      (node (ref "S5") (pin "4") (pinfunction "B1_4") (pintype "passive"))
      (node (ref "TTL") (pin "2") (pinfunction "2_2") (pintype "passive"))
      (node (ref "U1") (pin "1") (pinfunction "GND_1") (pintype "passive"))
      (node (ref "U1") (pin "3") (pinfunction "GND_3") (pintype "passive"))
      (node (ref "U4") (pin "2") (pinfunction "GND_2") (pintype "open_collector"))
      (node (ref "U5") (pin "2") (pinfunction "GND_2") (pintype "open_collector"))
      (node (ref "U6") (pin "2") (pinfunction "GND_2") (pintype "open_collector"))
      (node (ref "W2UART") (pin "5") (pinfunction "5_5") (pintype "passive"))
      (node (ref "W2UART") (pin "6") (pinfunction "6_6") (pintype "passive"))
      (node (ref "speed1") (pin "1") (pinfunction "1_1") (pintype "passive"))
      (node (ref "speed2") (pin "1") (pinfunction "1_1") (pintype "passive"))
      (node (ref "speed3") (pin "1") (pinfunction "1_1") (pintype "passive"))
      (node (ref "speed4") (pin "1") (pinfunction "1_1") (pintype "passive"))
    )
    (net (code "79") (name "GNDBAT") (class "Default")
      (node (ref "BAT") (pin "1") (pinfunction "1_1") (pintype "passive"))
      (node (ref "C2") (pin "1") (pinfunction "1_1") (pintype "passive"))
      (node (ref "C22") (pin "1") (pinfunction "1_1") (pintype "passive"))
      (node (ref "C3") (pin "2") (pinfunction "2_2") (pintype "passive"))
      (node (ref "C6") (pin "2") (pinfunction "2_2") (pintype "passive"))
      (node (ref "C7") (pin "1") (pinfunction "1_1") (pintype "passive"))
      (node (ref "FB1") (pin "1") (pinfunction "1_1") (pintype "passive"))
      (node (ref "FB2") (pin "1") (pinfunction "1_1") (pintype "passive"))
      (node (ref "Motor1") (pin "3") (pinfunction "3_3") (pintype "passive"))
      (node (ref "Motor1") (pin "4") (pinfunction "4_4") (pintype "passive"))
      (node (ref "Motor2") (pin "3") (pinfunction "3_3") (pintype "passive"))
      (node (ref "Motor2") (pin "4") (pinfunction "4_4") (pintype "passive"))
      (node (ref "Motor_1") (pin "2") (pinfunction "2_2") (pintype "passive"))
      (node (ref "Motor_2") (pin "2") (pinfunction "2_2") (pintype "passive"))
      (node (ref "P14") (pin "1") (pinfunction "1_1") (pintype "passive"))
      (node (ref "R11") (pin "2") (pinfunction "2_2") (pintype "passive"))
      (node (ref "U2") (pin "3") (pinfunction "GND_3") (pintype "open_collector"))
      (node (ref "U2") (pin "5") (pinfunction "ON/OFF_5") (pintype "open_collector"))
      (node (ref "U3") (pin "2") (pinfunction "GND_2") (pintype "open_collector"))
    )
    (net (code "80") (name "GNDCAM") (class "Default")
      (node (ref "C16") (pin "2") (pinfunction "2_2") (pintype "passive"))
      (node (ref "C17") (pin "1") (pinfunction "1_1") (pintype "passive"))
      (node (ref "Camera") (pin "14") (pinfunction "14_14") (pintype "passive"))
      (node (ref "Camera") (pin "4") (pinfunction "4_4") (pintype "passive"))
      (node (ref "FB3") (pin "2") (pinfunction "2_2") (pintype "passive"))
    )
    (net (code "81") (name "GNDOP") (class "Default")
      (node (ref "C20") (pin "2") (pinfunction "2_2") (pintype "passive"))
      (node (ref "C21") (pin "1") (pinfunction "1_1") (pintype "passive"))
      (node (ref "FB4") (pin "2") (pinfunction "2_2") (pintype "passive"))
      (node (ref "OPA1_1") (pin "1") (pinfunction "1_1") (pintype "passive"))
      (node (ref "OPA1_1") (pin "6") (pinfunction "6_6") (pintype "passive"))
      (node (ref "OPA1_2") (pin "2") (pinfunction "2_2") (pintype "passive"))
      (node (ref "OPA2_1") (pin "1") (pinfunction "1_1") (pintype "passive"))
      (node (ref "OPA2_1") (pin "6") (pinfunction "6_6") (pintype "passive"))
      (node (ref "OPA2_2") (pin "2") (pinfunction "2_2") (pintype "passive"))
      (node (ref "电磁接口1") (pin "1") (pinfunction "1_1") (pintype "passive"))
      (node (ref "电磁接口1") (pin "6") (pinfunction "6_6") (pintype "passive"))
      (node (ref "电磁接口2") (pin "1") (pinfunction "1_1") (pintype "passive"))
      (node (ref "电磁接口2") (pin "6") (pinfunction "6_6") (pintype "passive"))
    )
    (net (code "82") (name "GND_6.5V") (class "Default")
      (node (ref "C4") (pin "2") (pinfunction "2_2") (pintype "passive"))
      (node (ref "C5") (pin "1") (pinfunction "1_1") (pintype "passive"))
      (node (ref "FB1") (pin "2") (pinfunction "2_2") (pintype "passive"))
      (node (ref "Steer") (pin "3") (pinfunction "3_3") (pintype "passive"))
    )
    (net (code "83") (name "Net-(B1-Pad1)") (class "Default")
      (node (ref "B1") (pin "1") (pinfunction "1_1") (pintype "passive"))
      (node (ref "R18") (pin "2") (pinfunction "2_2") (pintype "passive"))
    )
    (net (code "84") (name "Net-(BAT-Pad2)") (class "Default")
      (node (ref "BAT") (pin "2") (pinfunction "2_2") (pintype "passive"))
      (node (ref "on/off") (pin "1") (pinfunction "1_1") (pintype "passive"))
    )
    (net (code "85") (name "Net-(D1-K)") (class "Default")
      (node (ref "C6") (pin "1") (pinfunction "1_1") (pintype "passive"))
      (node (ref "C7") (pin "2") (pinfunction "2_2") (pintype "passive"))
      (node (ref "D1") (pin "2") (pinfunction "K_2") (pintype "passive"))
      (node (ref "U3") (pin "1") (pinfunction "VIN_1") (pintype "open_collector"))
    )
    (net (code "86") (name "Net-(OPA1_1-Pad2)") (class "Default")
      (node (ref "OPA1_1") (pin "2") (pinfunction "2_2") (pintype "passive"))
      (node (ref "电磁接口1") (pin "5") (pinfunction "5_5") (pintype "passive"))
    )
    (net (code "87") (name "Net-(OPA1_1-Pad3)") (class "Default")
      (node (ref "OPA1_1") (pin "3") (pinfunction "3_3") (pintype "passive"))
      (node (ref "电磁接口1") (pin "4") (pinfunction "4_4") (pintype "passive"))
    )
    (net (code "88") (name "Net-(OPA1_1-Pad4)") (class "Default")
      (node (ref "OPA1_1") (pin "4") (pinfunction "4_4") (pintype "passive"))
      (node (ref "电磁接口1") (pin "3") (pinfunction "3_3") (pintype "passive"))
    )
    (net (code "89") (name "Net-(OPA1_1-Pad5)") (class "Default")
      (node (ref "OPA1_1") (pin "5") (pinfunction "5_5") (pintype "passive"))
      (node (ref "电磁接口1") (pin "2") (pinfunction "2_2") (pintype "passive"))
    )
    (net (code "90") (name "Net-(OPA2_1-Pad2)") (class "Default")
      (node (ref "OPA2_1") (pin "2") (pinfunction "2_2") (pintype "passive"))
      (node (ref "电磁接口2") (pin "5") (pinfunction "5_5") (pintype "passive"))
    )
    (net (code "91") (name "Net-(OPA2_1-Pad3)") (class "Default")
      (node (ref "OPA2_1") (pin "3") (pinfunction "3_3") (pintype "passive"))
      (node (ref "电磁接口2") (pin "4") (pinfunction "4_4") (pintype "passive"))
    )
    (net (code "92") (name "Net-(OPA2_1-Pad4)") (class "Default")
      (node (ref "OPA2_1") (pin "4") (pinfunction "4_4") (pintype "passive"))
      (node (ref "电磁接口2") (pin "3") (pinfunction "3_3") (pintype "passive"))
    )
    (net (code "93") (name "Net-(OPA2_1-Pad5)") (class "Default")
      (node (ref "OPA2_1") (pin "5") (pinfunction "5_5") (pintype "passive"))
      (node (ref "电磁接口2") (pin "2") (pinfunction "2_2") (pintype "passive"))
    )
    (net (code "94") (name "Net-(Q1-B)") (class "Default")
      (node (ref "Q1") (pin "3") (pinfunction "B_3") (pintype "passive"))
      (node (ref "R19") (pin "2") (pinfunction "2_2") (pintype "passive"))
    )
    (net (code "95") (name "Net-(Q1-C)") (class "Default")
      (node (ref "B1") (pin "2") (pinfunction "2_2") (pintype "passive"))
      (node (ref "Q1") (pin "2") (pinfunction "C_2") (pintype "passive"))
    )
    (net (code "96") (name "Net-(U2-FB)") (class "Default")
      (node (ref "P14") (pin "2") (pinfunction "2_2") (pintype "passive"))
      (node (ref "U2") (pin "4") (pinfunction "FB_4") (pintype "open_collector"))
    )
    (net (code "97") (name "Net-(U2-OUT)") (class "Default")
      (node (ref "L1") (pin "1") (pintype "open_collector"))
      (node (ref "U2") (pin "2") (pinfunction "OUT_2") (pintype "open_collector"))
    )
    (net (code "98") (name "VCC3V3") (class "Default")
      (node (ref "ADC") (pin "2") (pinfunction "2_2") (pintype "passive"))
      (node (ref "ADC") (pin "4") (pinfunction "4_4") (pintype "passive"))
      (node (ref "ADC") (pin "6") (pinfunction "6_6") (pintype "passive"))
      (node (ref "ADC") (pin "8") (pinfunction "8_8") (pintype "passive"))
      (node (ref "C12") (pin "1") (pinfunction "1_1") (pintype "passive"))
      (node (ref "C13") (pin "2") (pinfunction "2_2") (pintype "passive"))
      (node (ref "ICM20602") (pin "1") (pinfunction "1_1") (pintype "passive"))
      (node (ref "OLED/TFT") (pin "4") (pinfunction "4_4") (pintype "passive"))
      (node (ref "R12") (pin "1") (pinfunction "1_1") (pintype "passive"))
      (node (ref "R13") (pin "1") (pinfunction "1_1") (pintype "passive"))
      (node (ref "R14") (pin "1") (pinfunction "1_1") (pintype "passive"))
      (node (ref "R15") (pin "1") (pinfunction "1_1") (pintype "passive"))
      (node (ref "R16") (pin "1") (pinfunction "1_1") (pintype "passive"))
      (node (ref "R17") (pin "1") (pinfunction "1_1") (pintype "passive"))
      (node (ref "R18") (pin "1") (pinfunction "1_1") (pintype "passive"))
      (node (ref "U1") (pin "2") (pinfunction "VCC_2") (pintype "passive"))
      (node (ref "U1") (pin "4") (pinfunction "VCC_4") (pintype "passive"))
      (node (ref "U4") (pin "5") (pinfunction "OUT_5") (pintype "open_collector"))
      (node (ref "speed1") (pin "2") (pinfunction "2_2") (pintype "passive"))
      (node (ref "speed2") (pin "2") (pinfunction "2_2") (pintype "passive"))
      (node (ref "speed3") (pin "2") (pinfunction "2_2") (pintype "passive"))
      (node (ref "speed4") (pin "2") (pinfunction "2_2") (pintype "passive"))
    )
    (net (code "99") (name "VCC5V") (class "Default")
      (node (ref "C10") (pin "1") (pinfunction "1_1") (pintype "passive"))
      (node (ref "C11") (pin "2") (pinfunction "2_2") (pintype "passive"))
      (node (ref "C14") (pin "1") (pinfunction "1_1") (pintype "passive"))
      (node (ref "C15") (pin "2") (pinfunction "2_2") (pintype "passive"))
      (node (ref "C18") (pin "1") (pinfunction "1_1") (pintype "passive"))
      (node (ref "C19") (pin "2") (pinfunction "2_2") (pintype "passive"))
      (node (ref "C8") (pin "1") (pinfunction "1_1") (pintype "passive"))
      (node (ref "C9") (pin "2") (pinfunction "2_2") (pintype "passive"))
      (node (ref "TTL") (pin "1") (pinfunction "1_1") (pintype "passive"))
      (node (ref "U3") (pin "3") (pinfunction "VOUT_3") (pintype "open_collector"))
      (node (ref "U4") (pin "1") (pinfunction "IN_1") (pintype "open_collector"))
      (node (ref "U4") (pin "3") (pinfunction "EN_3") (pintype "open_collector"))
      (node (ref "U5") (pin "1") (pinfunction "IN_1") (pintype "open_collector"))
      (node (ref "U5") (pin "3") (pinfunction "EN_3") (pintype "open_collector"))
      (node (ref "U6") (pin "1") (pinfunction "IN_1") (pintype "open_collector"))
      (node (ref "U6") (pin "3") (pinfunction "EN_3") (pintype "open_collector"))
      (node (ref "W2UART") (pin "7") (pinfunction "7_7") (pintype "passive"))
      (node (ref "only_1") (pin "1") (pinfunction "1_1") (pintype "passive"))
    )
    (net (code "100") (name "VCCBAT") (class "Default")
      (node (ref "C2") (pin "2") (pinfunction "2_2") (pintype "passive"))
      (node (ref "C3") (pin "1") (pinfunction "1_1") (pintype "passive"))
      (node (ref "D1") (pin "1") (pinfunction "A_1") (pintype "passive"))
      (node (ref "Motor_1") (pin "1") (pinfunction "1_1") (pintype "passive"))
      (node (ref "Motor_2") (pin "1") (pinfunction "1_1") (pintype "passive"))
      (node (ref "R10") (pin "1") (pinfunction "1_1") (pintype "passive"))
      (node (ref "U2") (pin "1") (pinfunction "IN_1") (pintype "open_collector"))
      (node (ref "on/off") (pin "2") (pinfunction "2_2") (pintype "passive"))
      (node (ref "on/off") (pin "3") (pinfunction "3_3") (pintype "passive"))
    )
    (net (code "101") (name "VCCCAM") (class "Default")
      (node (ref "C16") (pin "1") (pinfunction "1_1") (pintype "passive"))
      (node (ref "C17") (pin "2") (pinfunction "2_2") (pintype "passive"))
      (node (ref "Camera") (pin "16") (pinfunction "16_16") (pintype "passive"))
      (node (ref "U5") (pin "5") (pinfunction "OUT_5") (pintype "open_collector"))
    )
    (net (code "102") (name "VCCOP") (class "Default")
      (node (ref "C20") (pin "1") (pinfunction "1_1") (pintype "passive"))
      (node (ref "C21") (pin "2") (pinfunction "2_2") (pintype "passive"))
      (node (ref "ONLY") (pin "1") (pinfunction "1_1") (pintype "passive"))
      (node (ref "U6") (pin "5") (pinfunction "OUT_5") (pintype "open_collector"))
    )
    (net (code "103") (name "VCCOPA") (class "Default")
      (node (ref "ONLY") (pin "2") (pinfunction "2_2") (pintype "passive"))
      (node (ref "OPA1_2") (pin "1") (pinfunction "1_1") (pintype "passive"))
      (node (ref "OPA2_2") (pin "1") (pinfunction "1_1") (pintype "passive"))
      (node (ref "only_1") (pin "2") (pinfunction "2_2") (pintype "passive"))
    )
    (net (code "104") (name "unconnected-(Camera-Pad10)") (class "Default")
      (node (ref "Camera") (pin "10") (pinfunction "10_10") (pintype "passive+no_connect"))
    )
    (net (code "105") (name "unconnected-(ICM20602-Pad7)") (class "Default")
      (node (ref "ICM20602") (pin "7") (pinfunction "7_7") (pintype "passive+no_connect"))
    )
    (net (code "106") (name "unconnected-(ICM20602-Pad8)") (class "Default")
      (node (ref "ICM20602") (pin "8") (pinfunction "8_8") (pintype "passive+no_connect"))
    )
    (net (code "107") (name "unconnected-(P10-X-Pad1)") (class "Default")
      (node (ref "P10") (pin "1") (pinfunction "X_1") (pintype "passive"))
    )
    (net (code "108") (name "unconnected-(P10-Y-Pad2)") (class "Default")
      (node (ref "P10") (pin "2") (pinfunction "Y_2") (pintype "passive"))
    )
    (net (code "109") (name "unconnected-(P11-X-Pad1)") (class "Default")
      (node (ref "P11") (pin "1") (pinfunction "X_1") (pintype "passive"))
    )
    (net (code "110") (name "unconnected-(P11-Y-Pad2)") (class "Default")
      (node (ref "P11") (pin "2") (pinfunction "Y_2") (pintype "passive"))
    )
    (net (code "111") (name "unconnected-(P12-X-Pad1)") (class "Default")
      (node (ref "P12") (pin "1") (pinfunction "X_1") (pintype "passive"))
    )
    (net (code "112") (name "unconnected-(P12-Y-Pad2)") (class "Default")
      (node (ref "P12") (pin "2") (pinfunction "Y_2") (pintype "passive"))
    )
    (net (code "113") (name "unconnected-(P13-X-Pad1)") (class "Default")
      (node (ref "P13") (pin "1") (pinfunction "X_1") (pintype "passive"))
    )
    (net (code "114") (name "unconnected-(P13-Y-Pad2)") (class "Default")
      (node (ref "P13") (pin "2") (pinfunction "Y_2") (pintype "passive"))
    )
    (net (code "115") (name "unconnected-(U1-00.8-Pad107)") (class "Default")
      (node (ref "U1") (pin "107") (pinfunction "00.8_107") (pintype "passive"))
    )
    (net (code "116") (name "unconnected-(U1-00.12-Pad109)") (class "Default")
      (node (ref "U1") (pin "109") (pinfunction "00.12_109") (pintype "passive"))
    )
    (net (code "117") (name "unconnected-(U1-11.2-Pad78)") (class "Default")
      (node (ref "U1") (pin "78") (pinfunction "11.2_78") (pintype "passive"))
    )
    (net (code "118") (name "unconnected-(U1-11.3-Pad79)") (class "Default")
      (node (ref "U1") (pin "79") (pinfunction "11.3_79") (pintype "passive"))
    )
    (net (code "119") (name "unconnected-(U1-11.6-Pad80)") (class "Default")
      (node (ref "U1") (pin "80") (pinfunction "11.6_80") (pintype "passive"))
    )
    (net (code "120") (name "unconnected-(U1-14.2-Pad69)") (class "Default")
      (node (ref "U1") (pin "69") (pinfunction "14.2_69") (pintype "passive+no_connect"))
    )
    (net (code "121") (name "unconnected-(U1-14.3-Pad70)") (class "Default")
      (node (ref "U1") (pin "70") (pinfunction "14.3_70") (pintype "passive+no_connect"))
    )
    (net (code "122") (name "unconnected-(U1-14.4-Pad71)") (class "Default")
      (node (ref "U1") (pin "71") (pinfunction "14.4_71") (pintype "passive+no_connect"))
    )
    (net (code "123") (name "unconnected-(U1-14.5-Pad72)") (class "Default")
      (node (ref "U1") (pin "72") (pinfunction "14.5_72") (pintype "passive+no_connect"))
    )
    (net (code "124") (name "unconnected-(U1-14.6-Pad73)") (class "Default")
      (node (ref "U1") (pin "73") (pinfunction "14.6_73") (pintype "passive+no_connect"))
    )
    (net (code "125") (name "unconnected-(U1-15.6-Pad64)") (class "Default")
      (node (ref "U1") (pin "64") (pinfunction "15.6_64") (pintype "passive"))
    )
    (net (code "126") (name "unconnected-(U1-15.7-Pad65)") (class "Default")
      (node (ref "U1") (pin "65") (pinfunction "15.7_65") (pintype "passive"))
    )
    (net (code "127") (name "unconnected-(U1-15.8-Pad66)") (class "Default")
      (node (ref "U1") (pin "66") (pinfunction "15.8_66") (pintype "passive"))
    )
    (net (code "128") (name "unconnected-(U1-20.2-Pad45)") (class "Default")
      (node (ref "U1") (pin "45") (pinfunction "20.2_45") (pintype "passive+no_connect"))
    )
    (net (code "129") (name "unconnected-(U1-20.6-Pad49)") (class "Default")
      (node (ref "U1") (pin "49") (pinfunction "20.6_49") (pintype "passive"))
    )
    (net (code "130") (name "unconnected-(U1-20.7-Pad50)") (class "Default")
      (node (ref "U1") (pin "50") (pinfunction "20.7_50") (pintype "passive"))
    )
    (net (code "131") (name "unconnected-(U1-20.8-Pad51)") (class "Default")
      (node (ref "U1") (pin "51") (pinfunction "20.8_51") (pintype "passive"))
    )
    (net (code "132") (name "unconnected-(U1-20.9-Pad52)") (class "Default")
      (node (ref "U1") (pin "52") (pinfunction "20.9_52") (pintype "passive"))
    )
    (net (code "133") (name "unconnected-(U1-20.10-Pad53)") (class "Default")
      (node (ref "U1") (pin "53") (pinfunction "20.10_53") (pintype "passive"))
    )
    (net (code "134") (name "unconnected-(U1-21.6-Pad42)") (class "Default")
      (node (ref "U1") (pin "42") (pinfunction "21.6_42") (pintype "passive+no_connect"))
    )
    (net (code "135") (name "unconnected-(U1-21.7-Pad43)") (class "Default")
      (node (ref "U1") (pin "43") (pinfunction "21.7_43") (pintype "passive+no_connect"))
    )
    (net (code "136") (name "unconnected-(U1-23.1-Pad33)") (class "Default")
      (node (ref "U1") (pin "33") (pinfunction "23.1_33") (pintype "passive"))
    )
    (net (code "137") (name "unconnected-(U1-32.4-Pad32)") (class "Default")
      (node (ref "U1") (pin "32") (pinfunction "32.4_32") (pintype "passive"))
    )
    (net (code "138") (name "unconnected-(U1-33.4-Pad22)") (class "Default")
      (node (ref "U1") (pin "22") (pinfunction "33.4_22") (pintype "passive"))
    )
    (net (code "139") (name "unconnected-(U1-33.5-Pad23)") (class "Default")
      (node (ref "U1") (pin "23") (pinfunction "33.5_23") (pintype "passive"))
    )
    (net (code "140") (name "unconnected-(U1-33.8-Pad26)") (class "Default")
      (node (ref "U1") (pin "26") (pinfunction "33.8_26") (pintype "passive"))
    )
    (net (code "141") (name "unconnected-(U1-33.11-Pad29)") (class "Default")
      (node (ref "U1") (pin "29") (pinfunction "33.11_29") (pintype "passive"))
    )
    (net (code "142") (name "unconnected-(U1-A24-Pad122)") (class "Default")
      (node (ref "U1") (pin "122") (pinfunction "A24_122") (pintype "passive"))
    )
    (net (code "143") (name "unconnected-(U1-A25-Pad121)") (class "Default")
      (node (ref "U1") (pin "121") (pinfunction "A25_121") (pintype "passive"))
    )
    (net (code "144") (name "unconnected-(U1-A35-Pad120)") (class "Default")
      (node (ref "U1") (pin "120") (pinfunction "A35_120") (pintype "passive"))
    )
    (net (code "145") (name "unconnected-(U1-A36-Pad119)") (class "Default")
      (node (ref "U1") (pin "119") (pinfunction "A36_119") (pintype "passive"))
    )
    (net (code "146") (name "unconnected-(U1-A37-Pad118)") (class "Default")
      (node (ref "U1") (pin "118") (pinfunction "A37_118") (pintype "passive"))
    )
    (net (code "147") (name "unconnected-(U1-A38-Pad117)") (class "Default")
      (node (ref "U1") (pin "117") (pinfunction "A38_117") (pintype "passive"))
    )
    (net (code "148") (name "unconnected-(U1-A39-Pad116)") (class "Default")
      (node (ref "U1") (pin "116") (pinfunction "A39_116") (pintype "passive"))
    )
    (net (code "149") (name "unconnected-(U1-A44-Pad115)") (class "Default")
      (node (ref "U1") (pin "115") (pinfunction "A44_115") (pintype "passive"))
    )
    (net (code "150") (name "unconnected-(U1-A45-Pad114)") (class "Default")
      (node (ref "U1") (pin "114") (pinfunction "A45_114") (pintype "passive"))
    )
    (net (code "151") (name "unconnected-(U1-A46-Pad113)") (class "Default")
      (node (ref "U1") (pin "113") (pinfunction "A46_113") (pintype "passive"))
    )
    (net (code "152") (name "unconnected-(U1-A47-Pad112)") (class "Default")
      (node (ref "U1") (pin "112") (pinfunction "A47_112") (pintype "passive"))
    )
    (net (code "153") (name "unconnected-(U1-A48-Pad111)") (class "Default")
      (node (ref "U1") (pin "111") (pinfunction "A48_111") (pintype "passive"))
    )
    (net (code "154") (name "unconnected-(U1-A49-Pad110)") (class "Default")
      (node (ref "U1") (pin "110") (pinfunction "A49_110") (pintype "passive"))
    )
    (net (code "155") (name "unconnected-(U1-ESR0-Pad48)") (class "Default")
      (node (ref "U1") (pin "48") (pinfunction "ESR0_48") (pintype "passive+no_connect"))
    )
    (net (code "156") (name "unconnected-(U1-ESR1-Pad47)") (class "Default")
      (node (ref "U1") (pin "47") (pinfunction "ESR1_47") (pintype "passive+no_connect"))
    )
    (net (code "157") (name "unconnected-(U4-NC-Pad4)") (class "Default")
      (node (ref "U4") (pin "4") (pinfunction "NC_4") (pintype "open_collector+no_connect"))
    )
    (net (code "158") (name "unconnected-(U5-NC-Pad4)") (class "Default")
      (node (ref "U5") (pin "4") (pinfunction "NC_4") (pintype "open_collector+no_connect"))
    )
    (net (code "159") (name "unconnected-(U6-NC-Pad4)") (class "Default")
      (node (ref "U6") (pin "4") (pinfunction "NC_4") (pintype "open_collector+no_connect"))
    )
    (net (code "160") (name "unconnected-(W2UART-Pad2)") (class "Default")
      (node (ref "W2UART") (pin "2") (pinfunction "2_2") (pintype "passive+no_connect"))
    )
    (net (code "161") (name "unconnected-(W2UART-Pad8)") (class "Default")
      (node (ref "W2UART") (pin "8") (pinfunction "8_8") (pintype "passive+no_connect"))
    )
    (net (code "162") (name "unconnected-(speed1-Pad5)") (class "Default")
      (node (ref "speed1") (pin "5") (pinfunction "5_5") (pintype "passive+no_connect"))
    )
    (net (code "163") (name "unconnected-(speed1-Pad6)") (class "Default")
      (node (ref "speed1") (pin "6") (pinfunction "6_6") (pintype "passive+no_connect"))
    )
    (net (code "164") (name "unconnected-(speed2-Pad5)") (class "Default")
      (node (ref "speed2") (pin "5") (pinfunction "5_5") (pintype "passive+no_connect"))
    )
    (net (code "165") (name "unconnected-(speed2-Pad6)") (class "Default")
      (node (ref "speed2") (pin "6") (pinfunction "6_6") (pintype "passive+no_connect"))
    )
    (net (code "166") (name "unconnected-(speed3-Pad5)") (class "Default")
      (node (ref "speed3") (pin "5") (pinfunction "5_5") (pintype "passive+no_connect"))
    )
    (net (code "167") (name "unconnected-(speed3-Pad6)") (class "Default")
      (node (ref "speed3") (pin "6") (pinfunction "6_6") (pintype "passive+no_connect"))
    )
    (net (code "168") (name "unconnected-(speed4-Pad5)") (class "Default")
      (node (ref "speed4") (pin "5") (pinfunction "5_5") (pintype "passive"))
    )
    (net (code "169") (name "unconnected-(speed4-Pad6)") (class "Default")
      (node (ref "speed4") (pin "6") (pinfunction "6_6") (pintype "passive"))
    )
  )
)
